# Servo_and_Encoders.net
KiCad netlist of a schematic drawn in Altium Designer
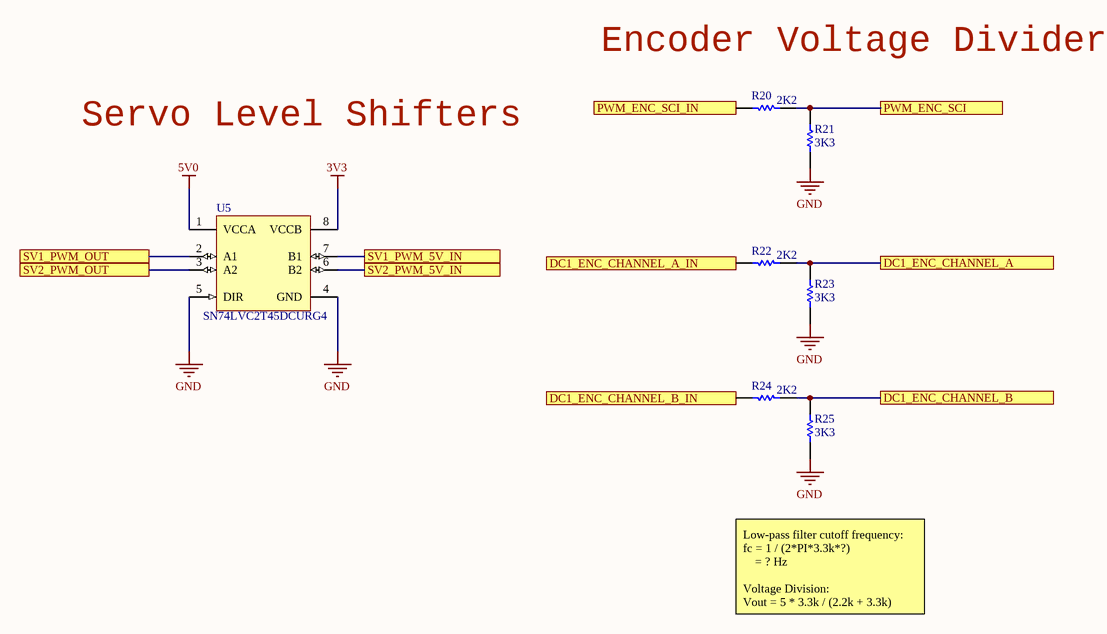
[diagram p0: Servo and Encoders.SchDoc]

(export (version "E")
  (design (tool "Eeschema 10.0.6"))
  (components
    (comp (ref "R20")
      (value "2K2")
      (footprint "RESC0603(1608)_N")
      (description "RES SMD 2.2K OHM 1% 1/10W 0603")
      (fields (field (name "MANUFACTURER") "Yageo") (field (name "TOLERANCE") "1%"))
      (libsource (lib "UWRT_Schematic_Library_2020") (part "RES_2K2_0603"))
    )
    (comp (ref "R21")
      (value "3K3")
      (footprint "RESC0603(1608)_N")
      (description "RES SMD 3.3K OHM 5% 1/10W 0603")
      (fields (field (name "MANUFACTURER") "Yageo") (field (name "TOLERANCE") "5%"))
      (libsource (lib "UWRT_Schematic_Library_2020") (part "RES_3K3_0603"))
    )
    (comp (ref "R22")
      (value "2K2")
      (footprint "RESC0603(1608)_N")
      (description "RES SMD 2.2K OHM 1% 1/10W 0603")
      (fields (field (name "MANUFACTURER") "Yageo") (field (name "TOLERANCE") "1%"))
      (libsource (lib "UWRT_Schematic_Library_2020") (part "RES_2K2_0603"))
    )
    (comp (ref "R23")
      (value "3K3")
      (footprint "RESC0603(1608)_N")
      (description "RES SMD 3.3K OHM 5% 1/10W 0603")
      (fields (field (name "MANUFACTURER") "Yageo") (field (name "TOLERANCE") "5%"))
      (libsource (lib "UWRT_Schematic_Library_2020") (part "RES_3K3_0603"))
    )
    (comp (ref "R24")
      (value "2K2")
      (footprint "RESC0603(1608)_N")
      (description "RES SMD 2.2K OHM 1% 1/10W 0603")
      (fields (field (name "MANUFACTURER") "Yageo") (field (name "TOLERANCE") "1%"))
      (libsource (lib "UWRT_Schematic_Library_2020") (part "RES_2K2_0603"))
    )
    (comp (ref "R25")
      (value "3K3")
      (footprint "RESC0603(1608)_N")
      (description "RES SMD 3.3K OHM 5% 1/10W 0603")
      (fields (field (name "MANUFACTURER") "Yageo") (field (name "TOLERANCE") "5%"))
      (libsource (lib "UWRT_Schematic_Library_2020") (part "RES_3K3_0603"))
    )
    (comp (ref "U5")
      (value "SN74LVC2T45DCURG4")
      (footprint "DCU0008A_L")
      (description "IC BIDIRECTIONAL LEVEL SHIFTER 8-VSSOP")
      (fields (field (name "GENERIC PART NUMBER") "SN74LVC2T45"))
      (libsource (lib "UWRT_Schematic_Library_2020") (part "IC_LVL_SHIFTER"))
    )
  )
  (nets
    (net (code "1") (name "/DC1_ENC_CHANNEL_A") (class "Default")
      (node (ref "R22") (pin "1") (pinfunction "1_1") (pintype "passive"))
      (node (ref "R23") (pin "2") (pinfunction "2_2") (pintype "passive"))
    )
    (net (code "2") (name "/DC1_ENC_CHANNEL_A_IN") (class "Default")
      (node (ref "R22") (pin "2") (pinfunction "2_2") (pintype "passive"))
    )
    (net (code "3") (name "/DC1_ENC_CHANNEL_B") (class "Default")
      (node (ref "R24") (pin "1") (pinfunction "1_1") (pintype "passive"))
      (node (ref "R25") (pin "2") (pinfunction "2_2") (pintype "passive"))
    )
    (net (code "4") (name "/DC1_ENC_CHANNEL_B_IN") (class "Default")
      (node (ref "R24") (pin "2") (pinfunction "2_2") (pintype "passive"))
    )
    (net (code "5") (name "/PWM_ENC_SCI") (class "Default")
      (node (ref "R20") (pin "1") (pinfunction "1_1") (pintype "passive"))
      (node (ref "R21") (pin "2") (pinfunction "2_2") (pintype "passive"))
    )
    (net (code "6") (name "/PWM_ENC_SCI_IN") (class "Default")
      (node (ref "R20") (pin "2") (pinfunction "2_2") (pintype "passive"))
    )
    (net (code "7") (name "/SV1_PWM_5V_IN") (class "Default")
      (node (ref "U5") (pin "7") (pinfunction "B1_7") (pintype "bidirectional"))
    )
    (net (code "8") (name "/SV1_PWM_OUT") (class "Default")
      (node (ref "U5") (pin "2") (pinfunction "A1_2") (pintype "bidirectional"))
    )
    (net (code "9") (name "/SV2_PWM_5V_IN") (class "Default")
      (node (ref "U5") (pin "6") (pinfunction "B2_6") (pintype "bidirectional"))
    )
    (net (code "10") (name "/SV2_PWM_OUT") (class "Default")
      (node (ref "U5") (pin "3") (pinfunction "A2_3") (pintype "bidirectional"))
    )
    (net (code "11") (name "3V3") (class "Default")
      (node (ref "U5") (pin "8") (pinfunction "VCCB_8") (pintype "power_in"))
    )
    (net (code "12") (name "5V0") (class "Default")
      (node (ref "U5") (pin "1") (pinfunction "VCCA_1") (pintype "power_in"))
    )
    (net (code "13") (name "GND") (class "Default")
      (node (ref "R21") (pin "1") (pinfunction "1_1") (pintype "passive"))
      (node (ref "R23") (pin "1") (pinfunction "1_1") (pintype "passive"))
      (node (ref "R25") (pin "1") (pinfunction "1_1") (pintype "passive"))
      (node (ref "U5") (pin "4") (pinfunction "GND_4") (pintype "power_in"))
      (node (ref "U5") (pin "5") (pinfunction "DIR_5") (pintype "input"))
    )
  )
)
